# Xbee_v1.net
KiCad netlist of a schematic drawn in EasyEDA Pro
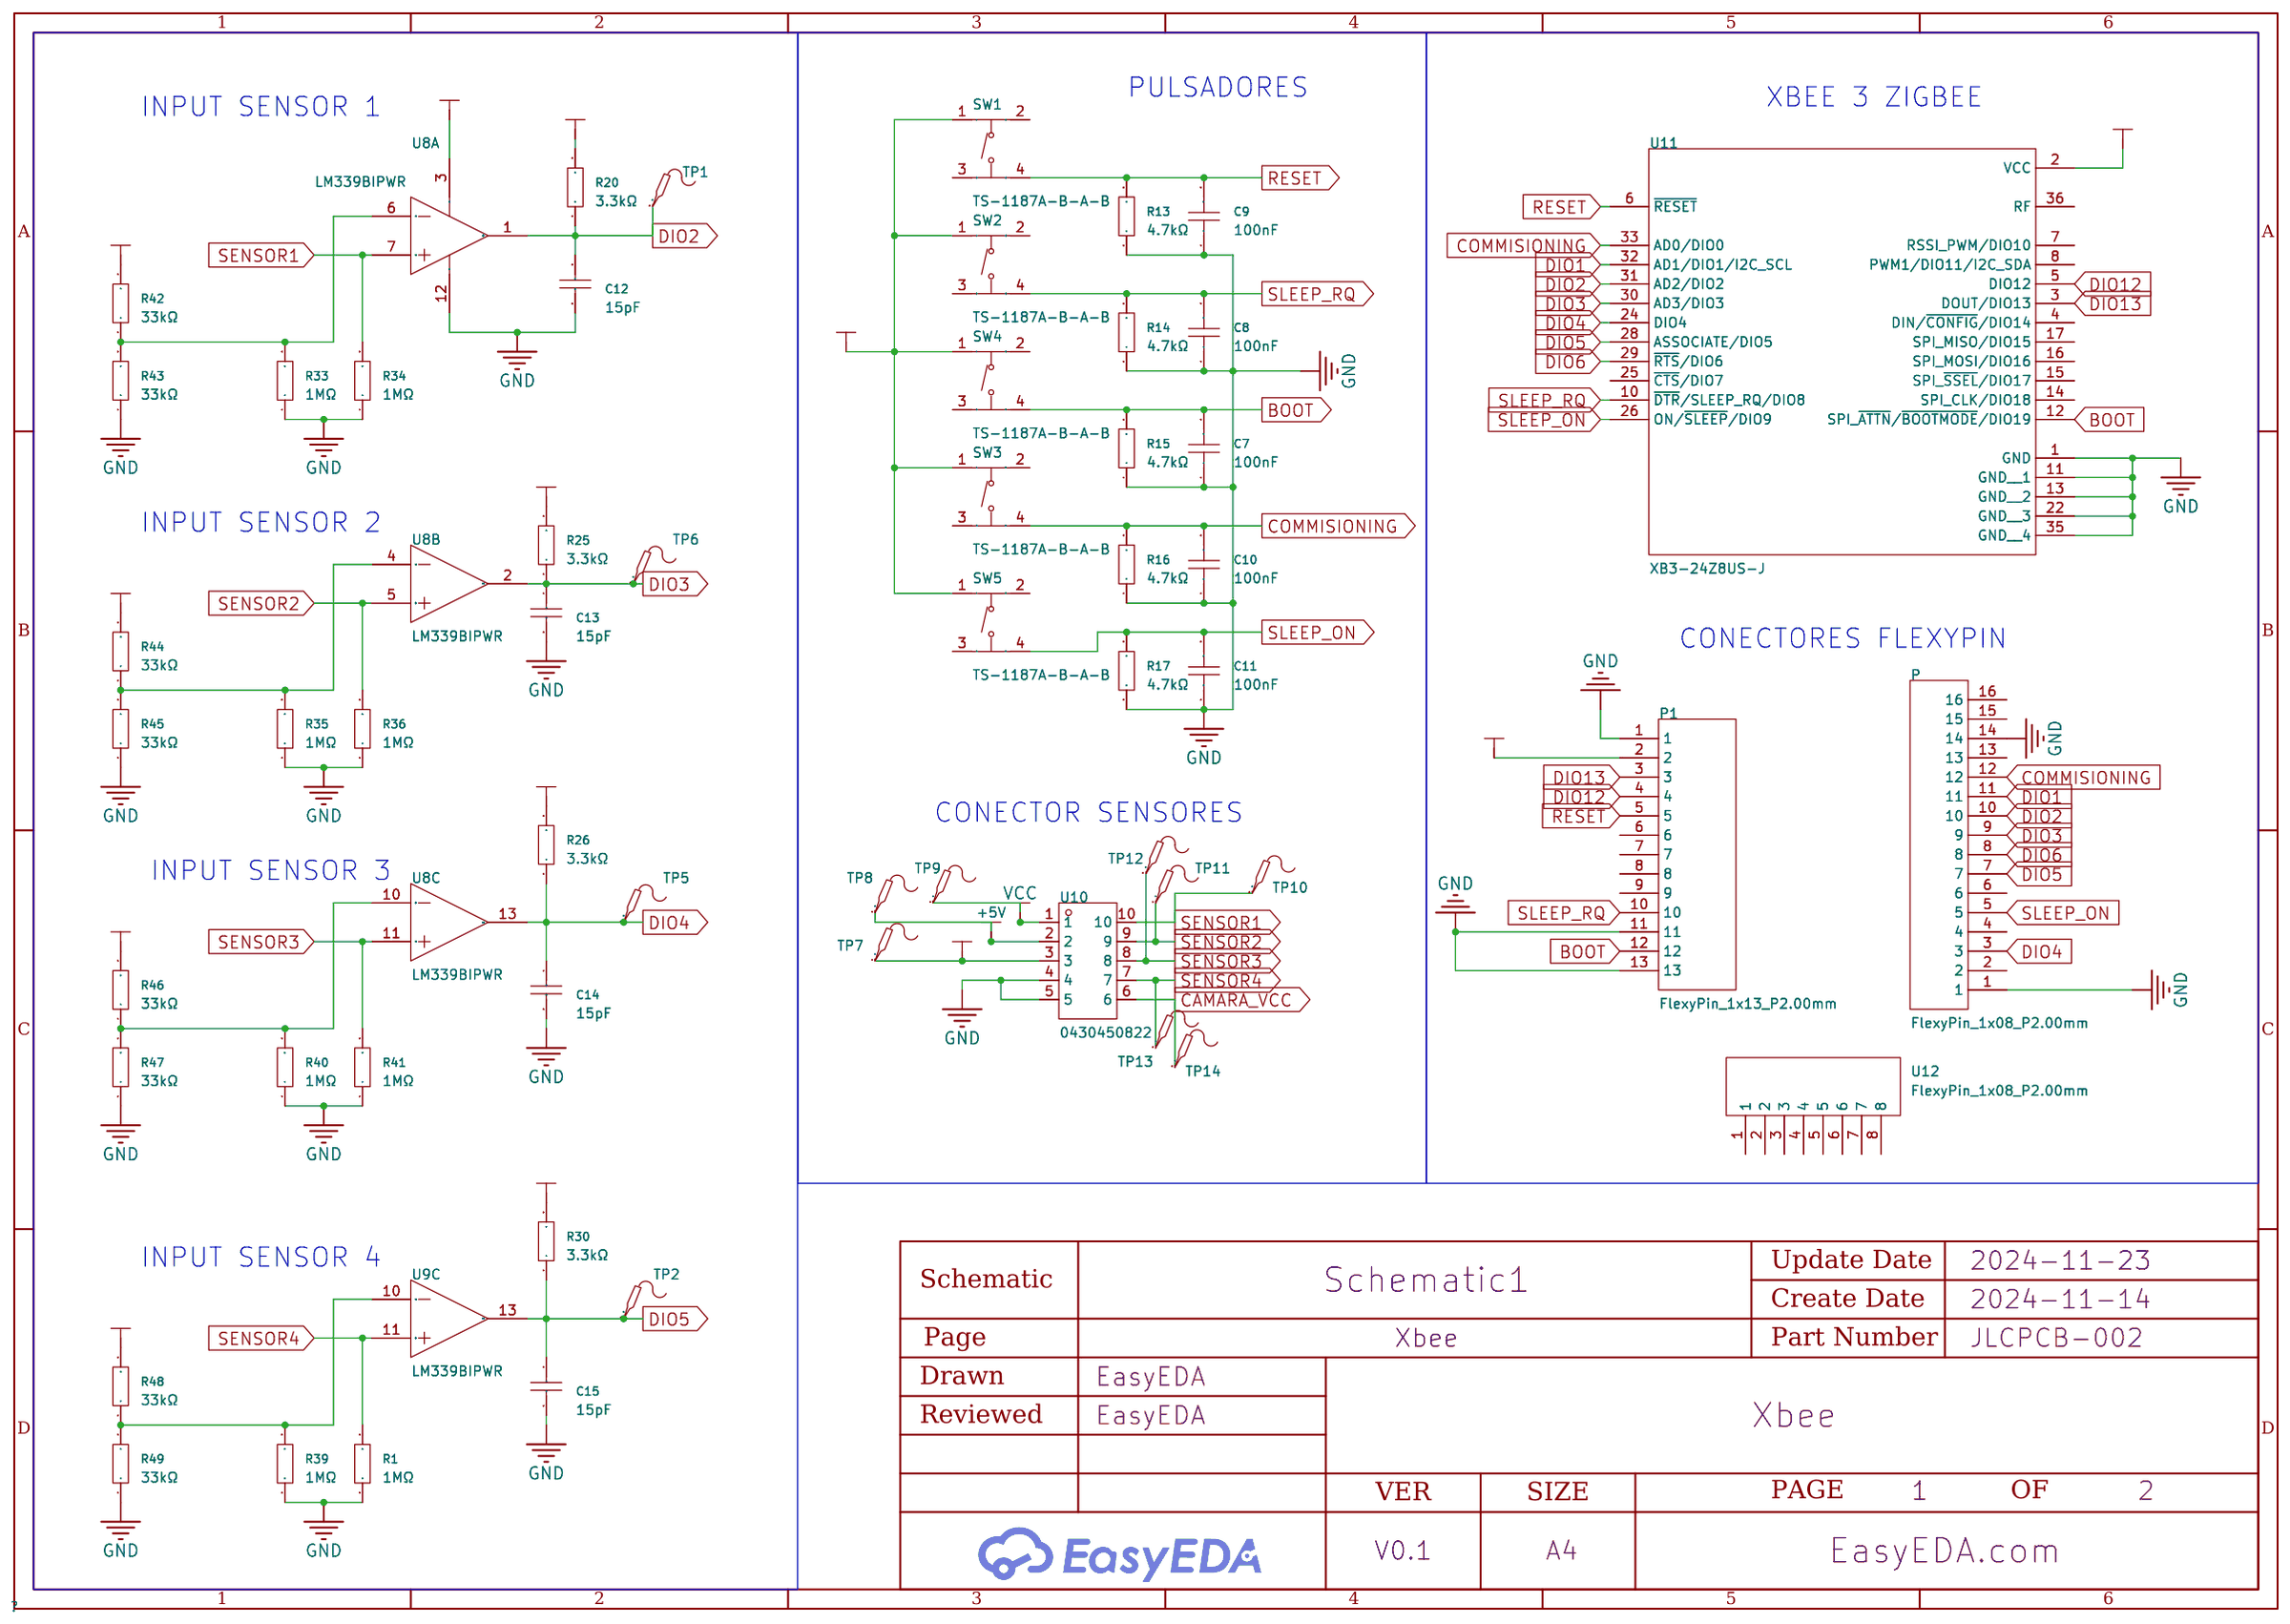
[diagram p0: Xbee]
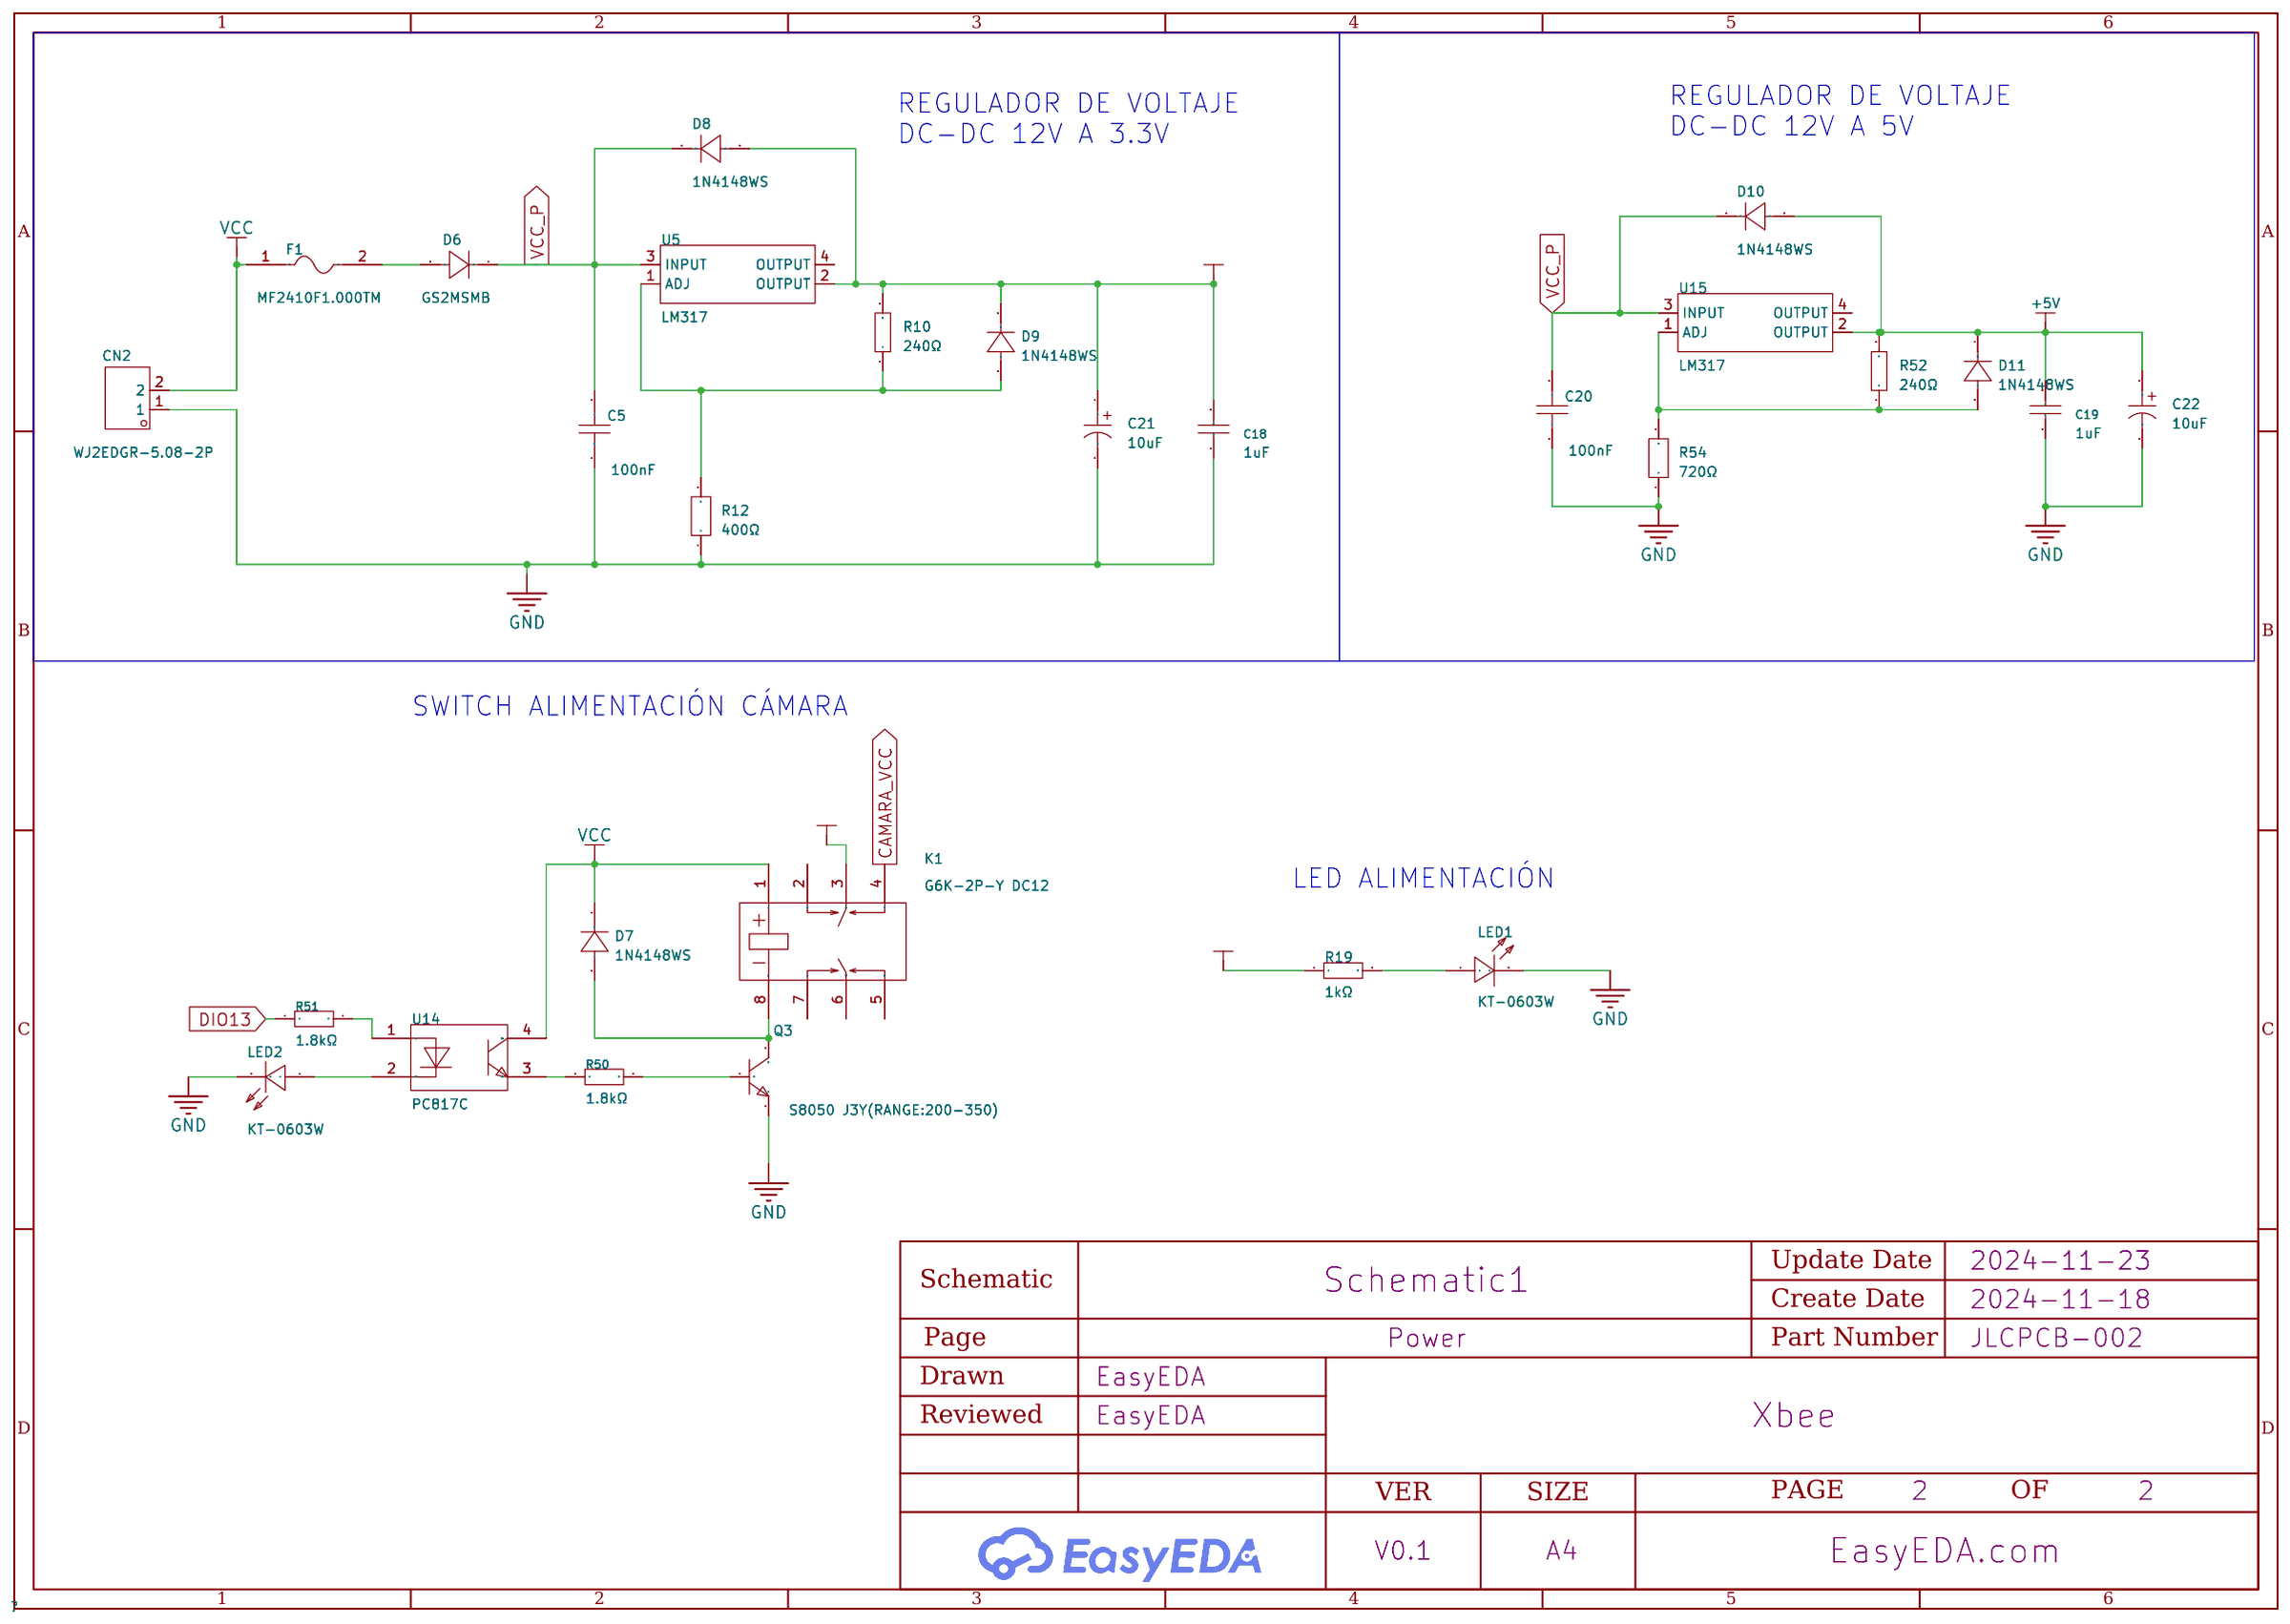
[diagram p1: Power]

(export (version "E")
  (design (tool "Eeschema 10.0.6"))
  (components
    (comp (ref "C7")
      (value "100nF")
      (footprint "easyedapro:C0603")
      (fields
        (field (name "Manufacturer Part") "CC0603KRX7R9BB104")
        (field (name "Manufacturer") "YAGEO(国巨)")
      )
      (libsource (lib "easyedapro") (part "CC0603KRX7R9BB104"))
    )
    (comp (ref "C8")
      (value "100nF")
      (footprint "easyedapro:C0603")
      (fields
        (field (name "Manufacturer Part") "CC0603KRX7R9BB104")
        (field (name "Manufacturer") "YAGEO(国巨)")
      )
      (libsource (lib "easyedapro") (part "CC0603KRX7R9BB104"))
    )
    (comp (ref "C9")
      (value "100nF")
      (footprint "easyedapro:C0603")
      (fields
        (field (name "Manufacturer Part") "CC0603KRX7R9BB104")
        (field (name "Manufacturer") "YAGEO(国巨)")
      )
      (libsource (lib "easyedapro") (part "CC0603KRX7R9BB104"))
    )
    (comp (ref "C10")
      (value "100nF")
      (footprint "easyedapro:C0603")
      (fields
        (field (name "Manufacturer Part") "CC0603KRX7R9BB104")
        (field (name "Manufacturer") "YAGEO(国巨)")
      )
      (libsource (lib "easyedapro") (part "CC0603KRX7R9BB104"))
    )
    (comp (ref "C11")
      (value "100nF")
      (footprint "easyedapro:C0603")
      (fields
        (field (name "Manufacturer Part") "CC0603KRX7R9BB104")
        (field (name "Manufacturer") "YAGEO(国巨)")
      )
      (libsource (lib "easyedapro") (part "CC0603KRX7R9BB104"))
    )
    (comp (ref "C12")
      (value "15pF")
      (footprint "easyedapro:C0603")
      (fields
        (field (name "Manufacturer Part") "CC0603JRNPO9BN150")
        (field (name "Manufacturer") "YAGEO(国巨)")
      )
      (libsource (lib "easyedapro") (part "CC0603JRNPO9BN150"))
    )
    (comp (ref "C13")
      (value "15pF")
      (footprint "easyedapro:C0603")
      (fields
        (field (name "Manufacturer Part") "CC0603JRNPO9BN150")
        (field (name "Manufacturer") "YAGEO(国巨)")
      )
      (libsource (lib "easyedapro") (part "CC0603JRNPO9BN150"))
    )
    (comp (ref "C14")
      (value "15pF")
      (footprint "easyedapro:C0603")
      (fields
        (field (name "Manufacturer Part") "CC0603JRNPO9BN150")
        (field (name "Manufacturer") "YAGEO(国巨)")
      )
      (libsource (lib "easyedapro") (part "CC0603JRNPO9BN150"))
    )
    (comp (ref "C15")
      (value "15pF")
      (footprint "easyedapro:C0603")
      (fields
        (field (name "Manufacturer Part") "CC0603JRNPO9BN150")
        (field (name "Manufacturer") "YAGEO(国巨)")
      )
      (libsource (lib "easyedapro") (part "CC0603JRNPO9BN150"))
    )
    (comp (ref "P")
      (value "FlexyPin_1x08_P2.00mm")
      (footprint "easyedapro:FlexyPin_1x16_P2.00mm")
      (libsource (lib "easyedapro") (part "FlexyPin_1x16_P2.00mm"))
    )
    (comp (ref "P1")
      (value "FlexyPin_1x13_P2.00mm")
      (footprint "easyedapro:FlexyPin_1x13_P2.00mm")
      (libsource (lib "easyedapro") (part "FlexyPin_1x13_P2.00mm"))
    )
    (comp (ref "R1")
      (value "1MΩ")
      (footprint "easyedapro:R1206")
      (fields
        (field (name "Manufacturer Part") "1206W4F1004T5E")
        (field (name "Manufacturer") "UNI-ROYAL(厚声)")
      )
      (libsource (lib "easyedapro") (part "1206W4F1004T5E"))
    )
    (comp (ref "R13")
      (value "4.7kΩ")
      (footprint "easyedapro:R0805")
      (fields
        (field (name "Manufacturer Part") "0805W8F4701T5E")
        (field (name "Manufacturer") "UNI-ROYAL(厚声)")
      )
      (libsource (lib "easyedapro") (part "0805W8F4701T5E"))
    )
    (comp (ref "R14")
      (value "4.7kΩ")
      (footprint "easyedapro:R0805")
      (fields
        (field (name "Manufacturer Part") "0805W8F4701T5E")
        (field (name "Manufacturer") "UNI-ROYAL(厚声)")
      )
      (libsource (lib "easyedapro") (part "0805W8F4701T5E"))
    )
    (comp (ref "R15")
      (value "4.7kΩ")
      (footprint "easyedapro:R0805")
      (fields
        (field (name "Manufacturer Part") "0805W8F4701T5E")
        (field (name "Manufacturer") "UNI-ROYAL(厚声)")
      )
      (libsource (lib "easyedapro") (part "0805W8F4701T5E"))
    )
    (comp (ref "R16")
      (value "4.7kΩ")
      (footprint "easyedapro:R0805")
      (fields
        (field (name "Manufacturer Part") "0805W8F4701T5E")
        (field (name "Manufacturer") "UNI-ROYAL(厚声)")
      )
      (libsource (lib "easyedapro") (part "0805W8F4701T5E"))
    )
    (comp (ref "R17")
      (value "4.7kΩ")
      (footprint "easyedapro:R0805")
      (fields
        (field (name "Manufacturer Part") "0805W8F4701T5E")
        (field (name "Manufacturer") "UNI-ROYAL(厚声)")
      )
      (libsource (lib "easyedapro") (part "0805W8F4701T5E"))
    )
    (comp (ref "R20")
      (value "3.3kΩ")
      (footprint "easyedapro:R0603")
      (fields
        (field (name "Manufacturer Part") "0603WAF3301T5E")
        (field (name "Manufacturer") "UNI-ROYAL(厚声)")
      )
      (libsource (lib "easyedapro") (part "0603WAF3301T5E"))
    )
    (comp (ref "R25")
      (value "3.3kΩ")
      (footprint "easyedapro:R0603")
      (fields
        (field (name "Manufacturer Part") "0603WAF3301T5E")
        (field (name "Manufacturer") "UNI-ROYAL(厚声)")
      )
      (libsource (lib "easyedapro") (part "0603WAF3301T5E"))
    )
    (comp (ref "R26")
      (value "3.3kΩ")
      (footprint "easyedapro:R0603")
      (fields
        (field (name "Manufacturer Part") "0603WAF3301T5E")
        (field (name "Manufacturer") "UNI-ROYAL(厚声)")
      )
      (libsource (lib "easyedapro") (part "0603WAF3301T5E"))
    )
    (comp (ref "R30")
      (value "3.3kΩ")
      (footprint "easyedapro:R0603")
      (fields
        (field (name "Manufacturer Part") "0603WAF3301T5E")
        (field (name "Manufacturer") "UNI-ROYAL(厚声)")
      )
      (libsource (lib "easyedapro") (part "0603WAF3301T5E"))
    )
    (comp (ref "R33")
      (value "1MΩ")
      (footprint "easyedapro:R1206")
      (fields
        (field (name "Manufacturer Part") "1206W4F1004T5E")
        (field (name "Manufacturer") "UNI-ROYAL(厚声)")
      )
      (libsource (lib "easyedapro") (part "1206W4F1004T5E"))
    )
    (comp (ref "R34")
      (value "1MΩ")
      (footprint "easyedapro:R1206")
      (fields
        (field (name "Manufacturer Part") "1206W4F1004T5E")
        (field (name "Manufacturer") "UNI-ROYAL(厚声)")
      )
      (libsource (lib "easyedapro") (part "1206W4F1004T5E"))
    )
    (comp (ref "R35")
      (value "1MΩ")
      (footprint "easyedapro:R1206")
      (fields
        (field (name "Manufacturer Part") "1206W4F1004T5E")
        (field (name "Manufacturer") "UNI-ROYAL(厚声)")
      )
      (libsource (lib "easyedapro") (part "1206W4F1004T5E"))
    )
    (comp (ref "R36")
      (value "1MΩ")
      (footprint "easyedapro:R1206")
      (fields
        (field (name "Manufacturer Part") "1206W4F1004T5E")
        (field (name "Manufacturer") "UNI-ROYAL(厚声)")
      )
      (libsource (lib "easyedapro") (part "1206W4F1004T5E"))
    )
    (comp (ref "R39")
      (value "1MΩ")
      (footprint "easyedapro:R1206")
      (fields
        (field (name "Manufacturer Part") "1206W4F1004T5E")
        (field (name "Manufacturer") "UNI-ROYAL(厚声)")
      )
      (libsource (lib "easyedapro") (part "1206W4F1004T5E"))
    )
    (comp (ref "R40")
      (value "1MΩ")
      (footprint "easyedapro:R1206")
      (fields
        (field (name "Manufacturer Part") "1206W4F1004T5E")
        (field (name "Manufacturer") "UNI-ROYAL(厚声)")
      )
      (libsource (lib "easyedapro") (part "1206W4F1004T5E"))
    )
    (comp (ref "R41")
      (value "1MΩ")
      (footprint "easyedapro:R1206")
      (fields
        (field (name "Manufacturer Part") "1206W4F1004T5E")
        (field (name "Manufacturer") "UNI-ROYAL(厚声)")
      )
      (libsource (lib "easyedapro") (part "1206W4F1004T5E"))
    )
    (comp (ref "R42")
      (value "33kΩ")
      (footprint "easyedapro:R0603")
      (fields
        (field (name "Manufacturer Part") "0603WAF3302T5E")
        (field (name "Manufacturer") "UNI-ROYAL(厚声)")
      )
      (libsource (lib "easyedapro") (part "0603WAF3302T5E"))
    )
    (comp (ref "R43")
      (value "33kΩ")
      (footprint "easyedapro:R0603")
      (fields
        (field (name "Manufacturer Part") "0603WAF3302T5E")
        (field (name "Manufacturer") "UNI-ROYAL(厚声)")
      )
      (libsource (lib "easyedapro") (part "0603WAF3302T5E"))
    )
    (comp (ref "R44")
      (value "33kΩ")
      (footprint "easyedapro:R0603")
      (fields
        (field (name "Manufacturer Part") "0603WAF3302T5E")
        (field (name "Manufacturer") "UNI-ROYAL(厚声)")
      )
      (libsource (lib "easyedapro") (part "0603WAF3302T5E"))
    )
    (comp (ref "R45")
      (value "33kΩ")
      (footprint "easyedapro:R0603")
      (fields
        (field (name "Manufacturer Part") "0603WAF3302T5E")
        (field (name "Manufacturer") "UNI-ROYAL(厚声)")
      )
      (libsource (lib "easyedapro") (part "0603WAF3302T5E"))
    )
    (comp (ref "R46")
      (value "33kΩ")
      (footprint "easyedapro:R0603")
      (fields
        (field (name "Manufacturer Part") "0603WAF3302T5E")
        (field (name "Manufacturer") "UNI-ROYAL(厚声)")
      )
      (libsource (lib "easyedapro") (part "0603WAF3302T5E"))
    )
    (comp (ref "R47")
      (value "33kΩ")
      (footprint "easyedapro:R0603")
      (fields
        (field (name "Manufacturer Part") "0603WAF3302T5E")
        (field (name "Manufacturer") "UNI-ROYAL(厚声)")
      )
      (libsource (lib "easyedapro") (part "0603WAF3302T5E"))
    )
    (comp (ref "R48")
      (value "33kΩ")
      (footprint "easyedapro:R0603")
      (fields
        (field (name "Manufacturer Part") "0603WAF3302T5E")
        (field (name "Manufacturer") "UNI-ROYAL(厚声)")
      )
      (libsource (lib "easyedapro") (part "0603WAF3302T5E"))
    )
    (comp (ref "R49")
      (value "33kΩ")
      (footprint "easyedapro:R0603")
      (fields
        (field (name "Manufacturer Part") "0603WAF3302T5E")
        (field (name "Manufacturer") "UNI-ROYAL(厚声)")
      )
      (libsource (lib "easyedapro") (part "0603WAF3302T5E"))
    )
    (comp (ref "SW1")
      (value "TS-1187A-B-A-B")
      (footprint "easyedapro:SW-SMD_4P-L5.1-W5.1-P3.70-LS6.5-TL_H1.5")
      (fields (field (name "Manufacturer") "XKB Connectivity(中国星坤)"))
      (libsource (lib "easyedapro") (part "TS-1187A-B-A-B"))
    )
    (comp (ref "SW2")
      (value "TS-1187A-B-A-B")
      (footprint "easyedapro:SW-SMD_4P-L5.1-W5.1-P3.70-LS6.5-TL_H1.5")
      (fields (field (name "Manufacturer") "XKB Connectivity(中国星坤)"))
      (libsource (lib "easyedapro") (part "TS-1187A-B-A-B"))
    )
    (comp (ref "SW3")
      (value "TS-1187A-B-A-B")
      (footprint "easyedapro:SW-SMD_4P-L5.1-W5.1-P3.70-LS6.5-TL_H1.5")
      (fields (field (name "Manufacturer") "XKB Connectivity(中国星坤)"))
      (libsource (lib "easyedapro") (part "TS-1187A-B-A-B"))
    )
    (comp (ref "SW4")
      (value "TS-1187A-B-A-B")
      (footprint "easyedapro:SW-SMD_4P-L5.1-W5.1-P3.70-LS6.5-TL_H1.5")
      (fields (field (name "Manufacturer") "XKB Connectivity(中国星坤)"))
      (libsource (lib "easyedapro") (part "TS-1187A-B-A-B"))
    )
    (comp (ref "SW5")
      (value "TS-1187A-B-A-B")
      (footprint "easyedapro:SW-SMD_4P-L5.1-W5.1-P3.70-LS6.5-TL_H1.5")
      (fields (field (name "Manufacturer") "XKB Connectivity(中国星坤)"))
      (libsource (lib "easyedapro") (part "TS-1187A-B-A-B"))
    )
    (comp (ref "TP1")
      (value "~")
      (footprint "easyedapro:Test-Point-0.5mm")
      (description "Test Point 测试点")
      (libsource (lib "easyedapro") (part "Test-Point"))
    )
    (comp (ref "TP2")
      (value "~")
      (footprint "easyedapro:Test-Point-0.5mm")
      (description "Test Point 测试点")
      (libsource (lib "easyedapro") (part "Test-Point"))
    )
    (comp (ref "TP5")
      (value "~")
      (footprint "easyedapro:Test-Point-0.5mm")
      (description "Test Point 测试点")
      (libsource (lib "easyedapro") (part "Test-Point"))
    )
    (comp (ref "TP6")
      (value "~")
      (footprint "easyedapro:Test-Point-0.5mm")
      (description "Test Point 测试点")
      (libsource (lib "easyedapro") (part "Test-Point"))
    )
    (comp (ref "TP7")
      (value "~")
      (footprint "easyedapro:Test-Point-0.5mm")
      (description "Test Point 测试点")
      (libsource (lib "easyedapro") (part "Test-Point"))
    )
    (comp (ref "TP8")
      (value "~")
      (footprint "easyedapro:Test-Point-0.5mm")
      (description "Test Point 测试点")
      (libsource (lib "easyedapro") (part "Test-Point"))
    )
    (comp (ref "TP9")
      (value "~")
      (footprint "easyedapro:Test-Point-0.5mm")
      (description "Test Point 测试点")
      (libsource (lib "easyedapro") (part "Test-Point"))
    )
    (comp (ref "TP10")
      (value "~")
      (footprint "easyedapro:Test-Point-0.5mm")
      (description "Test Point 测试点")
      (libsource (lib "easyedapro") (part "Test-Point"))
    )
    (comp (ref "TP11")
      (value "~")
      (footprint "easyedapro:Test-Point-0.5mm")
      (description "Test Point 测试点")
      (libsource (lib "easyedapro") (part "Test-Point"))
    )
    (comp (ref "TP12")
      (value "~")
      (footprint "easyedapro:Test-Point-0.5mm")
      (description "Test Point 测试点")
      (libsource (lib "easyedapro") (part "Test-Point"))
    )
    (comp (ref "TP13")
      (value "~")
      (footprint "easyedapro:Test-Point-0.5mm")
      (description "Test Point 测试点")
      (libsource (lib "easyedapro") (part "Test-Point"))
    )
    (comp (ref "TP14")
      (value "~")
      (footprint "easyedapro:Test-Point-0.5mm")
      (description "Test Point 测试点")
      (libsource (lib "easyedapro") (part "Test-Point"))
    )
    (comp (ref "U8")
      (value "LM339BIPWR")
      (footprint "easyedapro:TSSOP-14_L5.0-W4.4-P0.65-LS6.4-BL")
      (fields (field (name "Manufacturer") "TI(德州仪器)"))
      (libsource (lib "easyedapro") (part "LM339BIPWR"))
    )
    (comp (ref "U9")
      (value "LM339BIPWR")
      (footprint "easyedapro:TSSOP-14_L5.0-W4.4-P0.65-LS6.4-BL")
      (fields (field (name "Manufacturer") "TI(德州仪器)"))
      (libsource (lib "easyedapro") (part "LM339BIPWR"))
    )
    (comp (ref "U10")
      (value "0430450822")
      (footprint "easyedapro:CONN-TH_0430450822")
      (fields (field (name "Manufacturer") "MOLEX"))
      (libsource (lib "easyedapro") (part "0430450822"))
    )
    (comp (ref "U11") (value "XB3-24Z8US-J") (libsource (lib "easyedapro") (part "XB3-24Z8US-J")))
    (comp (ref "U12")
      (value "FlexyPin_1x08_P2.00mm")
      (footprint "easyedapro:FlexyPin_1x08_P2.00mm")
      (libsource (lib "easyedapro") (part "FlexyPin_1x08_P2.00mm"))
    )
    (comp (ref "C5")
      (value "100nF")
      (footprint "easyedapro:C0603")
      (fields
        (field (name "Manufacturer Part") "CC0603KRX7R9BB104")
        (field (name "Manufacturer") "YAGEO(国巨)")
      )
      (libsource (lib "easyedapro") (part "CC0603KRX7R9BB104"))
    )
    (comp (ref "C18")
      (value "1uF")
      (footprint "easyedapro:C0402")
      (fields
        (field (name "Manufacturer Part") "CL05A105KP5NNNC")
        (field (name "Manufacturer") "SAMSUNG(三星)")
      )
      (libsource (lib "easyedapro") (part "CL05A105KP5NNNC"))
    )
    (comp (ref "C19")
      (value "1uF")
      (footprint "easyedapro:C0402")
      (fields
        (field (name "Manufacturer Part") "CL05A105KP5NNNC")
        (field (name "Manufacturer") "SAMSUNG(三星)")
      )
      (libsource (lib "easyedapro") (part "CL05A105KP5NNNC"))
    )
    (comp (ref "C20")
      (value "100nF")
      (footprint "easyedapro:C0603")
      (fields
        (field (name "Manufacturer Part") "CC0603KRX7R9BB104")
        (field (name "Manufacturer") "YAGEO(国巨)")
      )
      (libsource (lib "easyedapro") (part "CC0603KRX7R9BB104"))
    )
    (comp (ref "C21")
      (value "10uF")
      (footprint "easyedapro:CAP-TH_BD5.0-P2.00-D0.6-FD")
      (fields (field (name "Manufacturer Part") "50V10uF CD110") (field (name "Manufacturer") "HRK(鸿瑞凯电子)"))
      (libsource (lib "easyedapro") (part "50V10UF CD110"))
    )
    (comp (ref "C22")
      (value "10uF")
      (footprint "easyedapro:CAP-TH_BD5.0-P2.00-D0.6-FD")
      (fields (field (name "Manufacturer Part") "50V10uF CD110") (field (name "Manufacturer") "HRK(鸿瑞凯电子)"))
      (libsource (lib "easyedapro") (part "50V10UF CD110"))
    )
    (comp (ref "CN2")
      (value "WJ2EDGR-5.08-2P")
      (footprint "easyedapro:CONN-TH_WJ2EDGR-5.08-2P")
      (fields (field (name "Manufacturer") "KANGNEX(康奈克斯电气)"))
      (libsource (lib "easyedapro") (part "WJ2EDGR-5.08-2P"))
    )
    (comp (ref "D6")
      (value "GS2MSMB")
      (footprint "easyedapro:SMB_L4.6-W3.5-LS5.3-RD")
      (fields (field (name "Manufacturer") "JKSEMI(金开盛)"))
      (libsource (lib "easyedapro") (part "GS2MSMB"))
    )
    (comp (ref "D7")
      (value "1N4148WS")
      (footprint "easyedapro:SOD-323_L1.8-W1.3-LS2.5-RD")
      (fields (field (name "Manufacturer") "JSMSEMI(杰盛微)"))
      (libsource (lib "easyedapro") (part "1N4148WS_C917117"))
    )
    (comp (ref "D8")
      (value "1N4148WS")
      (footprint "easyedapro:SOD-323_L1.8-W1.3-LS2.5-RD")
      (fields (field (name "Manufacturer") "JSMSEMI(杰盛微)"))
      (libsource (lib "easyedapro") (part "1N4148WS_C917117"))
    )
    (comp (ref "D9")
      (value "1N4148WS")
      (footprint "easyedapro:SOD-323_L1.8-W1.3-LS2.5-RD")
      (fields (field (name "Manufacturer") "JSMSEMI(杰盛微)"))
      (libsource (lib "easyedapro") (part "1N4148WS_C917117"))
    )
    (comp (ref "D10")
      (value "1N4148WS")
      (footprint "easyedapro:SOD-323_L1.8-W1.3-LS2.5-RD")
      (fields (field (name "Manufacturer") "JSMSEMI(杰盛微)"))
      (libsource (lib "easyedapro") (part "1N4148WS_C917117"))
    )
    (comp (ref "D11")
      (value "1N4148WS")
      (footprint "easyedapro:SOD-323_L1.8-W1.3-LS2.5-RD")
      (fields (field (name "Manufacturer") "JSMSEMI(杰盛微)"))
      (libsource (lib "easyedapro") (part "1N4148WS_C917117"))
    )
    (comp (ref "F1")
      (value "MF2410F1.000TM")
      (footprint "easyedapro:F2410")
      (fields (field (name "Manufacturer") "AEM"))
      (libsource (lib "easyedapro") (part "MF2410F1.000TM"))
    )
    (comp (ref "K1")
      (value "G6K-2P-Y DC12")
      (footprint "easyedapro:RELAY-TH_6S-2-4.5VG6K-2P-Y-12V")
      (fields (field (name "Manufacturer") "OMRON(欧姆龙)"))
      (libsource (lib "easyedapro") (part "G6K-2P-Y-12V"))
    )
    (comp (ref "LED1")
      (value "KT-0603W")
      (footprint "easyedapro:LED0603-R-RD_WHITE")
      (description "Emitted Color:White")
      (fields (field (name "Manufacturer") "KENTO"))
      (libsource (lib "easyedapro") (part "0603White light_C2290"))
    )
    (comp (ref "LED2")
      (value "KT-0603W")
      (footprint "easyedapro:LED0603-R-RD_WHITE")
      (description "Emitted Color:White")
      (fields (field (name "Manufacturer") "KENTO"))
      (libsource (lib "easyedapro") (part "0603White light_C2290"))
    )
    (comp (ref "Q3")
      (value "S8050 J3Y(RANGE:200-350)")
      (footprint "easyedapro:SOT-23-3_L3.0-W1.7-P0.95-LS2.9-BR")
      (fields (field (name "Manufacturer") "CJ(江苏长电/长晶)"))
      (libsource (lib "easyedapro") (part "S8050_C2146"))
    )
    (comp (ref "R10")
      (value "240Ω")
      (footprint "easyedapro:R0402")
      (fields (field (name "Manufacturer Part") "RC0402FR-07240RL") (field (name "Manufacturer") "YAGEO(国巨)"))
      (libsource (lib "easyedapro") (part "RC0402FR-07240RL"))
    )
    (comp (ref "R12")
      (value "400Ω")
      (footprint "easyedapro:R1206")
      (fields (field (name "Manufacturer Part") "RT1206BRD07400RL") (field (name "Manufacturer") "YAGEO(国巨)"))
      (libsource (lib "easyedapro") (part "RT1206BRD07400RL"))
    )
    (comp (ref "R19")
      (value "1kΩ")
      (footprint "easyedapro:R0603")
      (fields
        (field (name "Manufacturer Part") "0603WAF1001T5E")
        (field (name "Manufacturer") "UNI-ROYAL(厚声)")
      )
      (libsource (lib "easyedapro") (part "0603WAF1001T5E"))
    )
    (comp (ref "R50")
      (value "1.8kΩ")
      (footprint "easyedapro:R0402")
      (fields
        (field (name "Manufacturer Part") "0402WGF1801TCE")
        (field (name "Manufacturer") "UNI-ROYAL(厚声)")
      )
      (libsource (lib "easyedapro") (part "0402WGF1801TCE"))
    )
    (comp (ref "R51")
      (value "1.8kΩ")
      (footprint "easyedapro:R0402")
      (fields
        (field (name "Manufacturer Part") "0402WGF1801TCE")
        (field (name "Manufacturer") "UNI-ROYAL(厚声)")
      )
      (libsource (lib "easyedapro") (part "0402WGF1801TCE"))
    )
    (comp (ref "R52")
      (value "240Ω")
      (footprint "easyedapro:R0402")
      (fields (field (name "Manufacturer Part") "RC0402FR-07240RL") (field (name "Manufacturer") "YAGEO(国巨)"))
      (libsource (lib "easyedapro") (part "RC0402FR-07240RL"))
    )
    (comp (ref "R54")
      (value "720Ω")
      (footprint "easyedapro:R0805")
      (fields (field (name "Manufacturer Part") "Y1624720R000T9W") (field (name "Manufacturer") "VISHAY(威世)"))
      (libsource (lib "easyedapro") (part "Y1624720R000T9W"))
    )
    (comp (ref "U5")
      (value "LM317")
      (footprint "easyedapro:SOT-223-3_L6.7-W3.7-P2.30-LS7.0-BR")
      (fields (field (name "Manufacturer") "HXY MOSFET(华轩阳电子)"))
      (libsource (lib "easyedapro") (part "LM317_C7543014"))
    )
    (comp (ref "U14")
      (value "PC817C")
      (footprint "easyedapro:SMD-4_L6.5-W4.6-P2.54-LS10.3-TL")
      (fields (field (name "Manufacturer") "HXY MOSFET(华轩阳电子)"))
      (libsource (lib "easyedapro") (part "PC817C_C5451663"))
    )
    (comp (ref "U15")
      (value "LM317")
      (footprint "easyedapro:SOT-223-3_L6.7-W3.7-P2.30-LS7.0-BR")
      (fields (field (name "Manufacturer") "HXY MOSFET(华轩阳电子)"))
      (libsource (lib "easyedapro") (part "LM317_C7543014"))
    )
  )
  (nets
    (net (code "1") (name "+3.3V") (class "Default")
      (node (ref "C18") (pin "2") (pinfunction "2_2") (pintype "input"))
      (node (ref "C21") (pin "1") (pinfunction "1_1") (pintype "input"))
      (node (ref "D8") (pin "2") (pinfunction "A_2") (pintype "unspecified"))
      (node (ref "D9") (pin "1") (pinfunction "C_1") (pintype "unspecified"))
      (node (ref "K1") (pin "3") (pinfunction "3_3") (pintype "input"))
      (node (ref "P1") (pin "2") (pinfunction "2_2") (pintype "input"))
      (node (ref "R10") (pin "2") (pinfunction "2_2") (pintype "input"))
      (node (ref "R19") (pin "1") (pinfunction "1_1") (pintype "input"))
      (node (ref "R20") (pin "2") (pinfunction "2_2") (pintype "input"))
      (node (ref "R25") (pin "2") (pinfunction "2_2") (pintype "input"))
      (node (ref "R26") (pin "2") (pinfunction "2_2") (pintype "input"))
      (node (ref "R30") (pin "2") (pinfunction "2_2") (pintype "input"))
      (node (ref "R42") (pin "2") (pinfunction "2_2") (pintype "input"))
      (node (ref "R44") (pin "2") (pinfunction "2_2") (pintype "input"))
      (node (ref "R46") (pin "2") (pinfunction "2_2") (pintype "input"))
      (node (ref "R48") (pin "2") (pinfunction "2_2") (pintype "input"))
      (node (ref "SW1") (pin "1") (pinfunction "A_1") (pintype "unspecified"))
      (node (ref "SW2") (pin "1") (pinfunction "A_1") (pintype "unspecified"))
      (node (ref "SW3") (pin "1") (pinfunction "A_1") (pintype "unspecified"))
      (node (ref "SW4") (pin "1") (pinfunction "A_1") (pintype "unspecified"))
      (node (ref "SW5") (pin "1") (pinfunction "A_1") (pintype "unspecified"))
      (node (ref "TP7") (pin "1") (pinfunction "1_1") (pintype "unspecified"))
      (node (ref "U10") (pin "3") (pinfunction "3_3") (pintype "unspecified"))
      (node (ref "U11") (pin "2") (pinfunction "VCC_2") (pintype "unspecified"))
      (node (ref "U5") (pin "2") (pinfunction "OUTPUT_2") (pintype "unspecified"))
      (node (ref "U8") (pin "3") (pinfunction "VCC_3") (pintype "unspecified"))
    )
    (net (code "2") (name "+5V") (class "Default")
      (node (ref "C19") (pin "2") (pinfunction "2_2") (pintype "input"))
      (node (ref "C22") (pin "1") (pinfunction "1_1") (pintype "input"))
      (node (ref "D10") (pin "2") (pinfunction "A_2") (pintype "unspecified"))
      (node (ref "D11") (pin "1") (pinfunction "C_1") (pintype "unspecified"))
      (node (ref "R52") (pin "2") (pinfunction "2_2") (pintype "input"))
      (node (ref "TP8") (pin "1") (pinfunction "1_1") (pintype "unspecified"))
      (node (ref "U10") (pin "2") (pinfunction "2_2") (pintype "unspecified"))
      (node (ref "U15") (pin "2") (pinfunction "OUTPUT_2") (pintype "unspecified"))
    )
    (net (code "3") (name "BOOT") (class "Default")
      (node (ref "C7") (pin "2") (pinfunction "2_2") (pintype "input"))
      (node (ref "P1") (pin "12") (pinfunction "12_12") (pintype "input"))
      (node (ref "R15") (pin "2") (pinfunction "2_2") (pintype "input"))
      (node (ref "SW4") (pin "4") (pinfunction "D_4") (pintype "unspecified"))
      (node (ref "U11") (pin "12") (pinfunction "SPI_~{ATTN}/~{BOOTMODE}/DIO19_12") (pintype "bidirectional"))
    )
    (net (code "4") (name "CAMARA_VCC") (class "Default")
      (node (ref "K1") (pin "4") (pinfunction "4_4") (pintype "input"))
      (node (ref "TP14") (pin "1") (pinfunction "1_1") (pintype "unspecified"))
      (node (ref "U10") (pin "6") (pinfunction "6_6") (pintype "unspecified"))
    )
    (net (code "5") (name "COMMISIONING") (class "Default")
      (node (ref "C10") (pin "2") (pinfunction "2_2") (pintype "input"))
      (node (ref "P") (pin "12") (pinfunction "12_12") (pintype "input"))
      (node (ref "R16") (pin "2") (pinfunction "2_2") (pintype "input"))
      (node (ref "SW3") (pin "4") (pinfunction "D_4") (pintype "unspecified"))
      (node (ref "U11") (pin "33") (pinfunction "AD0/DIO0_33") (pintype "bidirectional"))
    )
    (net (code "6") (name "DIO1") (class "Default")
      (node (ref "P") (pin "11") (pinfunction "11_11") (pintype "input"))
      (node (ref "U11") (pin "32") (pinfunction "AD1/DIO1/I2C_SCL_32") (pintype "bidirectional"))
    )
    (net (code "7") (name "DIO2") (class "Default")
      (node (ref "C12") (pin "1") (pinfunction "1_1") (pintype "input"))
      (node (ref "P") (pin "10") (pinfunction "10_10") (pintype "input"))
      (node (ref "R20") (pin "1") (pinfunction "1_1") (pintype "input"))
      (node (ref "TP1") (pin "1") (pinfunction "1_1") (pintype "unspecified"))
      (node (ref "U11") (pin "31") (pinfunction "AD2/DIO2_31") (pintype "bidirectional"))
      (node (ref "U8") (pin "1") (pinfunction "OUT1_1") (pintype "output"))
    )
    (net (code "8") (name "DIO3") (class "Default")
      (node (ref "C13") (pin "1") (pinfunction "1_1") (pintype "input"))
      (node (ref "P") (pin "9") (pinfunction "9_9") (pintype "input"))
      (node (ref "R25") (pin "1") (pinfunction "1_1") (pintype "input"))
      (node (ref "TP6") (pin "1") (pinfunction "1_1") (pintype "unspecified"))
      (node (ref "U11") (pin "30") (pinfunction "AD3/DIO3_30") (pintype "bidirectional"))
      (node (ref "U8") (pin "2") (pinfunction "OUT2_2") (pintype "output"))
    )
    (net (code "9") (name "DIO4") (class "Default")
      (node (ref "C14") (pin "1") (pinfunction "1_1") (pintype "input"))
      (node (ref "P") (pin "3") (pinfunction "3_3") (pintype "input"))
      (node (ref "R26") (pin "1") (pinfunction "1_1") (pintype "input"))
      (node (ref "TP5") (pin "1") (pinfunction "1_1") (pintype "unspecified"))
      (node (ref "U11") (pin "24") (pinfunction "DIO4_24") (pintype "bidirectional"))
      (node (ref "U8") (pin "13") (pinfunction "OUT3_13") (pintype "output"))
    )
    (net (code "10") (name "DIO5") (class "Default")
      (node (ref "C15") (pin "1") (pinfunction "1_1") (pintype "input"))
      (node (ref "P") (pin "7") (pinfunction "7_7") (pintype "input"))
      (node (ref "R30") (pin "1") (pinfunction "1_1") (pintype "input"))
      (node (ref "TP2") (pin "1") (pinfunction "1_1") (pintype "unspecified"))
      (node (ref "U11") (pin "28") (pinfunction "ASSOCIATE/DIO5_28") (pintype "bidirectional"))
      (node (ref "U9") (pin "13") (pinfunction "OUT3_13") (pintype "output"))
    )
    (net (code "11") (name "DIO6") (class "Default")
      (node (ref "P") (pin "8") (pinfunction "8_8") (pintype "input"))
      (node (ref "U11") (pin "29") (pinfunction "~{RTS}/DIO6_29") (pintype "bidirectional"))
    )
    (net (code "12") (name "DIO12") (class "Default")
      (node (ref "P1") (pin "4") (pinfunction "4_4") (pintype "input"))
      (node (ref "U11") (pin "5") (pinfunction "DIO12_5") (pintype "bidirectional"))
    )
    (net (code "13") (name "DIO13") (class "Default")
      (node (ref "P1") (pin "3") (pinfunction "3_3") (pintype "input"))
      (node (ref "R51") (pin "1") (pinfunction "1_1") (pintype "input"))
      (node (ref "U11") (pin "3") (pinfunction "DOUT/DIO13_3") (pintype "bidirectional"))
    )
    (net (code "14") (name "GND") (class "Default")
      (node (ref "C10") (pin "1") (pinfunction "1_1") (pintype "input"))
      (node (ref "C11") (pin "1") (pinfunction "1_1") (pintype "input"))
      (node (ref "C12") (pin "2") (pinfunction "2_2") (pintype "input"))
      (node (ref "C13") (pin "2") (pinfunction "2_2") (pintype "input"))
      (node (ref "C14") (pin "2") (pinfunction "2_2") (pintype "input"))
      (node (ref "C15") (pin "2") (pinfunction "2_2") (pintype "input"))
      (node (ref "C18") (pin "1") (pinfunction "1_1") (pintype "input"))
      (node (ref "C19") (pin "1") (pinfunction "1_1") (pintype "input"))
      (node (ref "C20") (pin "1") (pinfunction "1_1") (pintype "input"))
      (node (ref "C21") (pin "2") (pinfunction "2_2") (pintype "input"))
      (node (ref "C22") (pin "2") (pinfunction "2_2") (pintype "input"))
      (node (ref "C5") (pin "1") (pinfunction "1_1") (pintype "input"))
      (node (ref "C7") (pin "1") (pinfunction "1_1") (pintype "input"))
      (node (ref "C8") (pin "1") (pinfunction "1_1") (pintype "input"))
      (node (ref "C9") (pin "1") (pinfunction "1_1") (pintype "input"))
      (node (ref "CN2") (pin "1") (pinfunction "1_1") (pintype "unspecified"))
      (node (ref "LED1") (pin "2") (pinfunction "K_2") (pintype "unspecified"))
      (node (ref "LED2") (pin "2") (pinfunction "K_2") (pintype "unspecified"))
      (node (ref "P") (pin "1") (pinfunction "1_1") (pintype "input"))
      (node (ref "P") (pin "14") (pinfunction "14_14") (pintype "input"))
      (node (ref "P1") (pin "1") (pinfunction "1_1") (pintype "input"))
      (node (ref "P1") (pin "11") (pinfunction "11_11") (pintype "input"))
      (node (ref "P1") (pin "13") (pinfunction "13_13") (pintype "input"))
      (node (ref "Q3") (pin "2") (pinfunction "E_2") (pintype "unspecified"))
      (node (ref "R1") (pin "1") (pinfunction "1_1") (pintype "input"))
      (node (ref "R12") (pin "1") (pinfunction "1_1") (pintype "unspecified"))
      (node (ref "R13") (pin "1") (pinfunction "1_1") (pintype "input"))
      (node (ref "R14") (pin "1") (pinfunction "1_1") (pintype "input"))
      (node (ref "R15") (pin "1") (pinfunction "1_1") (pintype "input"))
      (node (ref "R16") (pin "1") (pinfunction "1_1") (pintype "input"))
      (node (ref "R17") (pin "1") (pinfunction "1_1") (pintype "input"))
      (node (ref "R33") (pin "1") (pinfunction "1_1") (pintype "input"))
      (node (ref "R34") (pin "1") (pinfunction "1_1") (pintype "input"))
      (node (ref "R35") (pin "1") (pinfunction "1_1") (pintype "input"))
      (node (ref "R36") (pin "1") (pinfunction "1_1") (pintype "input"))
      (node (ref "R39") (pin "1") (pinfunction "1_1") (pintype "input"))
      (node (ref "R40") (pin "1") (pinfunction "1_1") (pintype "input"))
      (node (ref "R41") (pin "1") (pinfunction "1_1") (pintype "input"))
      (node (ref "R43") (pin "1") (pinfunction "1_1") (pintype "input"))
      (node (ref "R45") (pin "1") (pinfunction "1_1") (pintype "input"))
      (node (ref "R47") (pin "1") (pinfunction "1_1") (pintype "input"))
      (node (ref "R49") (pin "1") (pinfunction "1_1") (pintype "input"))
      (node (ref "R54") (pin "1") (pinfunction "1_1") (pintype "unspecified"))
      (node (ref "U10") (pin "4") (pinfunction "4_4") (pintype "unspecified"))
      (node (ref "U10") (pin "5") (pinfunction "5_5") (pintype "unspecified"))
      (node (ref "U11") (pin "1") (pinfunction "GND_1") (pintype "unspecified"))
      (node (ref "U11") (pin "11") (pinfunction "GND__1_11") (pintype "unspecified"))
      (node (ref "U11") (pin "13") (pinfunction "GND__2_13") (pintype "unspecified"))
      (node (ref "U11") (pin "22") (pinfunction "GND__3_22") (pintype "unspecified"))
      (node (ref "U11") (pin "35") (pinfunction "GND__4_35") (pintype "unspecified"))
      (node (ref "U8") (pin "12") (pinfunction "GND_12") (pintype "unspecified"))
    )
    (net (code "15") (name "Net-(D6-A)") (class "Default")
      (node (ref "D6") (pin "2") (pinfunction "A_2") (pintype "unspecified"))
      (node (ref "F1") (pin "2") (pinfunction "2_2") (pintype "unspecified"))
    )
    (net (code "16") (name "Net-(D7-A)") (class "Default")
      (node (ref "D7") (pin "2") (pinfunction "A_2") (pintype "unspecified"))
      (node (ref "K1") (pin "8") (pinfunction "8_8") (pintype "input"))
      (node (ref "Q3") (pin "3") (pinfunction "C_3") (pintype "unspecified"))
    )
    (net (code "17") (name "Net-(D9-A)") (class "Default")
      (node (ref "D9") (pin "2") (pinfunction "A_2") (pintype "unspecified"))
      (node (ref "R10") (pin "1") (pinfunction "1_1") (pintype "input"))
      (node (ref "R12") (pin "2") (pinfunction "2_2") (pintype "unspecified"))
      (node (ref "U5") (pin "1") (pinfunction "ADJ_1") (pintype "unspecified"))
    )
    (net (code "18") (name "Net-(D11-A)") (class "Default")
      (node (ref "D11") (pin "2") (pinfunction "A_2") (pintype "unspecified"))
      (node (ref "R52") (pin "1") (pinfunction "1_1") (pintype "input"))
      (node (ref "R54") (pin "2") (pinfunction "2_2") (pintype "unspecified"))
      (node (ref "U15") (pin "1") (pinfunction "ADJ_1") (pintype "unspecified"))
    )
    (net (code "19") (name "Net-(LED1-A)") (class "Default")
      (node (ref "LED1") (pin "1") (pinfunction "A_1") (pintype "unspecified"))
      (node (ref "R19") (pin "2") (pinfunction "2_2") (pintype "input"))
    )
    (net (code "20") (name "Net-(LED2-A)") (class "Default")
      (node (ref "LED2") (pin "1") (pinfunction "A_1") (pintype "unspecified"))
      (node (ref "U14") (pin "2") (pinfunction "Cathode_2") (pintype "unspecified"))
    )
    (net (code "21") (name "Net-(Q3-B)") (class "Default")
      (node (ref "Q3") (pin "1") (pinfunction "B_1") (pintype "unspecified"))
      (node (ref "R50") (pin "2") (pinfunction "2_2") (pintype "input"))
    )
    (net (code "22") (name "Net-(U8A-IN1-)") (class "Default")
      (node (ref "R33") (pin "2") (pinfunction "2_2") (pintype "input"))
      (node (ref "R42") (pin "1") (pinfunction "1_1") (pintype "input"))
      (node (ref "R43") (pin "2") (pinfunction "2_2") (pintype "input"))
      (node (ref "U8") (pin "6") (pinfunction "IN1-_6") (pintype "unspecified"))
    )
    (net (code "23") (name "Net-(U8B-IN2-)") (class "Default")
      (node (ref "R35") (pin "2") (pinfunction "2_2") (pintype "input"))
      (node (ref "R44") (pin "1") (pinfunction "1_1") (pintype "input"))
      (node (ref "R45") (pin "2") (pinfunction "2_2") (pintype "input"))
      (node (ref "U8") (pin "4") (pinfunction "IN2-_4") (pintype "unspecified"))
    )
    (net (code "24") (name "Net-(U8C-IN3-)") (class "Default")
      (node (ref "R40") (pin "2") (pinfunction "2_2") (pintype "input"))
      (node (ref "R46") (pin "1") (pinfunction "1_1") (pintype "input"))
      (node (ref "R47") (pin "2") (pinfunction "2_2") (pintype "input"))
      (node (ref "U8") (pin "10") (pinfunction "IN3-_10") (pintype "unspecified"))
    )
    (net (code "25") (name "Net-(U9C-IN3-)") (class "Default")
      (node (ref "R39") (pin "2") (pinfunction "2_2") (pintype "input"))
      (node (ref "R48") (pin "1") (pinfunction "1_1") (pintype "input"))
      (node (ref "R49") (pin "2") (pinfunction "2_2") (pintype "input"))
      (node (ref "U9") (pin "10") (pinfunction "IN3-_10") (pintype "unspecified"))
    )
    (net (code "26") (name "Net-(U14-Anode)") (class "Default")
      (node (ref "R51") (pin "2") (pinfunction "2_2") (pintype "input"))
      (node (ref "U14") (pin "1") (pinfunction "Anode_1") (pintype "unspecified"))
    )
    (net (code "27") (name "Net-(U14-Emitter)") (class "Default")
      (node (ref "R50") (pin "1") (pinfunction "1_1") (pintype "input"))
      (node (ref "U14") (pin "3") (pinfunction "Emitter_3") (pintype "unspecified"))
    )
    (net (code "28") (name "RESET") (class "Default")
      (node (ref "C9") (pin "2") (pinfunction "2_2") (pintype "input"))
      (node (ref "P1") (pin "5") (pinfunction "5_5") (pintype "input"))
      (node (ref "R13") (pin "2") (pinfunction "2_2") (pintype "input"))
      (node (ref "SW1") (pin "4") (pinfunction "D_4") (pintype "unspecified"))
      (node (ref "U11") (pin "6") (pinfunction "~{RESET}_6") (pintype "input"))
    )
    (net (code "29") (name "SENSOR1") (class "Default")
      (node (ref "R34") (pin "2") (pinfunction "2_2") (pintype "input"))
      (node (ref "TP10") (pin "1") (pinfunction "1_1") (pintype "unspecified"))
      (node (ref "U10") (pin "10") (pinfunction "10_10") (pintype "unspecified"))
      (node (ref "U8") (pin "7") (pinfunction "IN1+_7") (pintype "unspecified"))
    )
    (net (code "30") (name "SENSOR2") (class "Default")
      (node (ref "R36") (pin "2") (pinfunction "2_2") (pintype "input"))
      (node (ref "TP11") (pin "1") (pinfunction "1_1") (pintype "unspecified"))
      (node (ref "U10") (pin "9") (pinfunction "9_9") (pintype "unspecified"))
      (node (ref "U8") (pin "5") (pinfunction "IN2+_5") (pintype "unspecified"))
    )
    (net (code "31") (name "SENSOR3") (class "Default")
      (node (ref "R41") (pin "2") (pinfunction "2_2") (pintype "input"))
      (node (ref "TP12") (pin "1") (pinfunction "1_1") (pintype "unspecified"))
      (node (ref "U10") (pin "8") (pinfunction "8_8") (pintype "unspecified"))
      (node (ref "U8") (pin "11") (pinfunction "IN3+_11") (pintype "unspecified"))
    )
    (net (code "32") (name "SENSOR4") (class "Default")
      (node (ref "R1") (pin "2") (pinfunction "2_2") (pintype "input"))
      (node (ref "TP13") (pin "1") (pinfunction "1_1") (pintype "unspecified"))
      (node (ref "U10") (pin "7") (pinfunction "7_7") (pintype "unspecified"))
      (node (ref "U9") (pin "11") (pinfunction "IN3+_11") (pintype "unspecified"))
    )
    (net (code "33") (name "SLEEP_ON") (class "Default")
      (node (ref "C11") (pin "2") (pinfunction "2_2") (pintype "input"))
      (node (ref "P") (pin "5") (pinfunction "5_5") (pintype "input"))
      (node (ref "R17") (pin "2") (pinfunction "2_2") (pintype "input"))
      (node (ref "SW5") (pin "4") (pinfunction "D_4") (pintype "unspecified"))
      (node (ref "U11") (pin "26") (pinfunction "ON/~{SLEEP}/DIO9_26") (pintype "bidirectional"))
    )
    (net (code "34") (name "SLEEP_RQ") (class "Default")
      (node (ref "C8") (pin "2") (pinfunction "2_2") (pintype "input"))
      (node (ref "P1") (pin "10") (pinfunction "10_10") (pintype "input"))
      (node (ref "R14") (pin "2") (pinfunction "2_2") (pintype "input"))
      (node (ref "SW2") (pin "4") (pinfunction "D_4") (pintype "unspecified"))
      (node (ref "U11") (pin "10") (pinfunction "~{DTR}/SLEEP_RQ/DIO8_10") (pintype "bidirectional"))
    )
    (net (code "35") (name "VCC") (class "Default")
      (node (ref "CN2") (pin "2") (pinfunction "2_2") (pintype "unspecified"))
      (node (ref "D7") (pin "1") (pinfunction "C_1") (pintype "unspecified"))
      (node (ref "F1") (pin "1") (pinfunction "1_1") (pintype "unspecified"))
      (node (ref "K1") (pin "1") (pinfunction "1_1") (pintype "input"))
      (node (ref "TP9") (pin "1") (pinfunction "1_1") (pintype "unspecified"))
      (node (ref "U10") (pin "1") (pinfunction "1_1") (pintype "unspecified"))
      (node (ref "U14") (pin "4") (pinfunction "Collector_4") (pintype "unspecified"))
    )
    (net (code "36") (name "VCC_P") (class "Default")
      (node (ref "C20") (pin "2") (pinfunction "2_2") (pintype "input"))
      (node (ref "C5") (pin "2") (pinfunction "2_2") (pintype "input"))
      (node (ref "D10") (pin "1") (pinfunction "C_1") (pintype "unspecified"))
      (node (ref "D6") (pin "1") (pinfunction "C_1") (pintype "unspecified"))
      (node (ref "D8") (pin "1") (pinfunction "C_1") (pintype "unspecified"))
      (node (ref "U15") (pin "3") (pinfunction "INPUT_3") (pintype "unspecified"))
      (node (ref "U5") (pin "3") (pinfunction "INPUT_3") (pintype "unspecified"))
    )
    (net (code "37") (name "unconnected-(K1-Pad2)") (class "Default")
      (node (ref "K1") (pin "2") (pinfunction "2_2") (pintype "input"))
    )
    (net (code "38") (name "unconnected-(K1-Pad5)") (class "Default")
      (node (ref "K1") (pin "5") (pinfunction "5_5") (pintype "input"))
    )
    (net (code "39") (name "unconnected-(K1-Pad6)") (class "Default")
      (node (ref "K1") (pin "6") (pinfunction "6_6") (pintype "input"))
    )
    (net (code "40") (name "unconnected-(K1-Pad7)") (class "Default")
      (node (ref "K1") (pin "7") (pinfunction "7_7") (pintype "input"))
    )
    (net (code "41") (name "unconnected-(P-Pad2)") (class "Default")
      (node (ref "P") (pin "2") (pinfunction "2_2") (pintype "input"))
    )
    (net (code "42") (name "unconnected-(P-Pad4)") (class "Default")
      (node (ref "P") (pin "4") (pinfunction "4_4") (pintype "input"))
    )
    (net (code "43") (name "unconnected-(P-Pad6)") (class "Default")
      (node (ref "P") (pin "6") (pinfunction "6_6") (pintype "input"))
    )
    (net (code "44") (name "unconnected-(P-Pad13)") (class "Default")
      (node (ref "P") (pin "13") (pinfunction "13_13") (pintype "input"))
    )
    (net (code "45") (name "unconnected-(P-Pad15)") (class "Default")
      (node (ref "P") (pin "15") (pinfunction "15_15") (pintype "input"))
    )
    (net (code "46") (name "unconnected-(P-Pad16)") (class "Default")
      (node (ref "P") (pin "16") (pinfunction "16_16") (pintype "input"))
    )
    (net (code "47") (name "unconnected-(P1-Pad6)") (class "Default")
      (node (ref "P1") (pin "6") (pinfunction "6_6") (pintype "input"))
    )
    (net (code "48") (name "unconnected-(P1-Pad7)") (class "Default")
      (node (ref "P1") (pin "7") (pinfunction "7_7") (pintype "input"))
    )
    (net (code "49") (name "unconnected-(P1-Pad8)") (class "Default")
      (node (ref "P1") (pin "8") (pinfunction "8_8") (pintype "input"))
    )
    (net (code "50") (name "unconnected-(P1-Pad9)") (class "Default")
      (node (ref "P1") (pin "9") (pinfunction "9_9") (pintype "input"))
    )
    (net (code "51") (name "unconnected-(SW1-B-Pad2)") (class "Default")
      (node (ref "SW1") (pin "2") (pinfunction "B_2") (pintype "unspecified"))
    )
    (net (code "52") (name "unconnected-(SW1-C-Pad3)") (class "Default")
      (node (ref "SW1") (pin "3") (pinfunction "C_3") (pintype "unspecified"))
    )
    (net (code "53") (name "unconnected-(SW2-B-Pad2)") (class "Default")
      (node (ref "SW2") (pin "2") (pinfunction "B_2") (pintype "unspecified"))
    )
    (net (code "54") (name "unconnected-(SW2-C-Pad3)") (class "Default")
      (node (ref "SW2") (pin "3") (pinfunction "C_3") (pintype "unspecified"))
    )
    (net (code "55") (name "unconnected-(SW3-B-Pad2)") (class "Default")
      (node (ref "SW3") (pin "2") (pinfunction "B_2") (pintype "unspecified"))
    )
    (net (code "56") (name "unconnected-(SW3-C-Pad3)") (class "Default")
      (node (ref "SW3") (pin "3") (pinfunction "C_3") (pintype "unspecified"))
    )
    (net (code "57") (name "unconnected-(SW4-B-Pad2)") (class "Default")
      (node (ref "SW4") (pin "2") (pinfunction "B_2") (pintype "unspecified"))
    )
    (net (code "58") (name "unconnected-(SW4-C-Pad3)") (class "Default")
      (node (ref "SW4") (pin "3") (pinfunction "C_3") (pintype "unspecified"))
    )
    (net (code "59") (name "unconnected-(SW5-B-Pad2)") (class "Default")
      (node (ref "SW5") (pin "2") (pinfunction "B_2") (pintype "unspecified"))
    )
    (net (code "60") (name "unconnected-(SW5-C-Pad3)") (class "Default")
      (node (ref "SW5") (pin "3") (pinfunction "C_3") (pintype "unspecified"))
    )
    (net (code "61") (name "unconnected-(U5-OUTPUT-Pad4)") (class "Default")
      (node (ref "U5") (pin "4") (pinfunction "OUTPUT_4") (pintype "unspecified"))
    )
    (net (code "62") (name "unconnected-(U11-DIN{slash}~{CONFIG}{slash}DIO14-Pad4)") (class "Default")
      (node (ref "U11") (pin "4") (pinfunction "DIN/~{CONFIG}/DIO14_4") (pintype "bidirectional"))
    )
    (net (code "63") (name "unconnected-(U11-PWM1{slash}DIO11{slash}I2C_SDA-Pad8)") (class "Default")
      (node (ref "U11") (pin "8") (pinfunction "PWM1/DIO11/I2C_SDA_8") (pintype "bidirectional"))
    )
    (net (code "64") (name "unconnected-(U11-RF-Pad36)") (class "Default")
      (node (ref "U11") (pin "36") (pinfunction "RF_36") (pintype "bidirectional"))
    )
    (net (code "65") (name "unconnected-(U11-RSSI_PWM{slash}DIO10-Pad7)") (class "Default")
      (node (ref "U11") (pin "7") (pinfunction "RSSI_PWM/DIO10_7") (pintype "bidirectional"))
    )
    (net (code "66") (name "unconnected-(U11-SPI_CLK{slash}DIO18-Pad14)") (class "Default")
      (node (ref "U11") (pin "14") (pinfunction "SPI_CLK/DIO18_14") (pintype "bidirectional"))
    )
    (net (code "67") (name "unconnected-(U11-SPI_MISO{slash}DIO15-Pad17)") (class "Default")
      (node (ref "U11") (pin "17") (pinfunction "SPI_MISO/DIO15_17") (pintype "bidirectional"))
    )
    (net (code "68") (name "unconnected-(U11-SPI_MOSI{slash}DIO16-Pad16)") (class "Default")
      (node (ref "U11") (pin "16") (pinfunction "SPI_MOSI/DIO16_16") (pintype "bidirectional"))
    )
    (net (code "69") (name "unconnected-(U11-SPI_~{SSEL}{slash}DIO17-Pad15)") (class "Default")
      (node (ref "U11") (pin "15") (pinfunction "SPI_~{SSEL}/DIO17_15") (pintype "bidirectional"))
    )
    (net (code "70") (name "unconnected-(U11-~{CTS}{slash}DIO7-Pad25)") (class "Default")
      (node (ref "U11") (pin "25") (pinfunction "~{CTS}/DIO7_25") (pintype "bidirectional"))
    )
    (net (code "71") (name "unconnected-(U12-Pad1)") (class "Default")
      (node (ref "U12") (pin "1") (pinfunction "1_1") (pintype "input"))
    )
    (net (code "72") (name "unconnected-(U12-Pad2)") (class "Default")
      (node (ref "U12") (pin "2") (pinfunction "2_2") (pintype "input"))
    )
    (net (code "73") (name "unconnected-(U12-Pad3)") (class "Default")
      (node (ref "U12") (pin "3") (pinfunction "3_3") (pintype "input"))
    )
    (net (code "74") (name "unconnected-(U12-Pad4)") (class "Default")
      (node (ref "U12") (pin "4") (pinfunction "4_4") (pintype "input"))
    )
    (net (code "75") (name "unconnected-(U12-Pad5)") (class "Default")
      (node (ref "U12") (pin "5") (pinfunction "5_5") (pintype "input"))
    )
    (net (code "76") (name "unconnected-(U12-Pad6)") (class "Default")
      (node (ref "U12") (pin "6") (pinfunction "6_6") (pintype "input"))
    )
    (net (code "77") (name "unconnected-(U12-Pad7)") (class "Default")
      (node (ref "U12") (pin "7") (pinfunction "7_7") (pintype "input"))
    )
    (net (code "78") (name "unconnected-(U12-Pad8)") (class "Default")
      (node (ref "U12") (pin "8") (pinfunction "8_8") (pintype "input"))
    )
    (net (code "79") (name "unconnected-(U15-OUTPUT-Pad4)") (class "Default")
      (node (ref "U15") (pin "4") (pinfunction "OUTPUT_4") (pintype "unspecified"))
    )
  )
)
